# Pasa_altas.net
KiCad netlist of a schematic drawn in Altium Designer
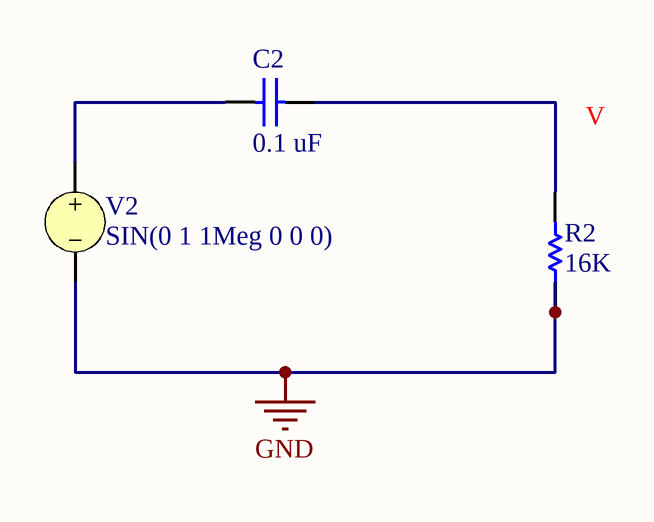
[diagram p0: Pasa_altas.SchDoc]

(export (version "E")
  (design (tool "Eeschema 10.0.6"))
  (components
    (comp (ref "C2")
      (value "0.1 uF")
      (description "Capacitor")
      (libsource (lib "Simulation Generic Components") (part "Capacitor"))
    )
    (comp (ref "R2")
      (value "16K")
      (description "Resistor")
      (libsource (lib "Simulation Generic Components") (part "Resistor"))
    )
    (comp (ref "V2")
      (value "SIN(0 1 1Meg 0 0 0)")
      (description "Voltage Source")
      (fields (field (name "PUBLISHER") "Altium Limited"))
      (libsource (lib "Simulation Generic Components") (part "VSRC"))
    )
  )
  (nets
    (net (code "1") (name "GND") (class "Default")
      (node (ref "R2") (pin "1") (pinfunction "1_1") (pintype "passive"))
      (node (ref "V2") (pin "2") (pinfunction "2_2") (pintype "passive"))
    )
    (net (code "2") (name "Net-(C2-Pad1)") (class "Default")
      (node (ref "C2") (pin "1") (pinfunction "1_1") (pintype "passive"))
      (node (ref "V2") (pin "1") (pinfunction "1_1") (pintype "passive"))
    )
    (net (code "3") (name "Net-(C2-Pad2)") (class "Default")
      (node (ref "C2") (pin "2") (pinfunction "2_2") (pintype "passive"))
      (node (ref "R2") (pin "2") (pinfunction "2_2") (pintype "passive"))
    )
  )
)
